# OZ440-SE100-CAR003_sheet7.net
KiCad netlist of a schematic drawn in Altium Designer
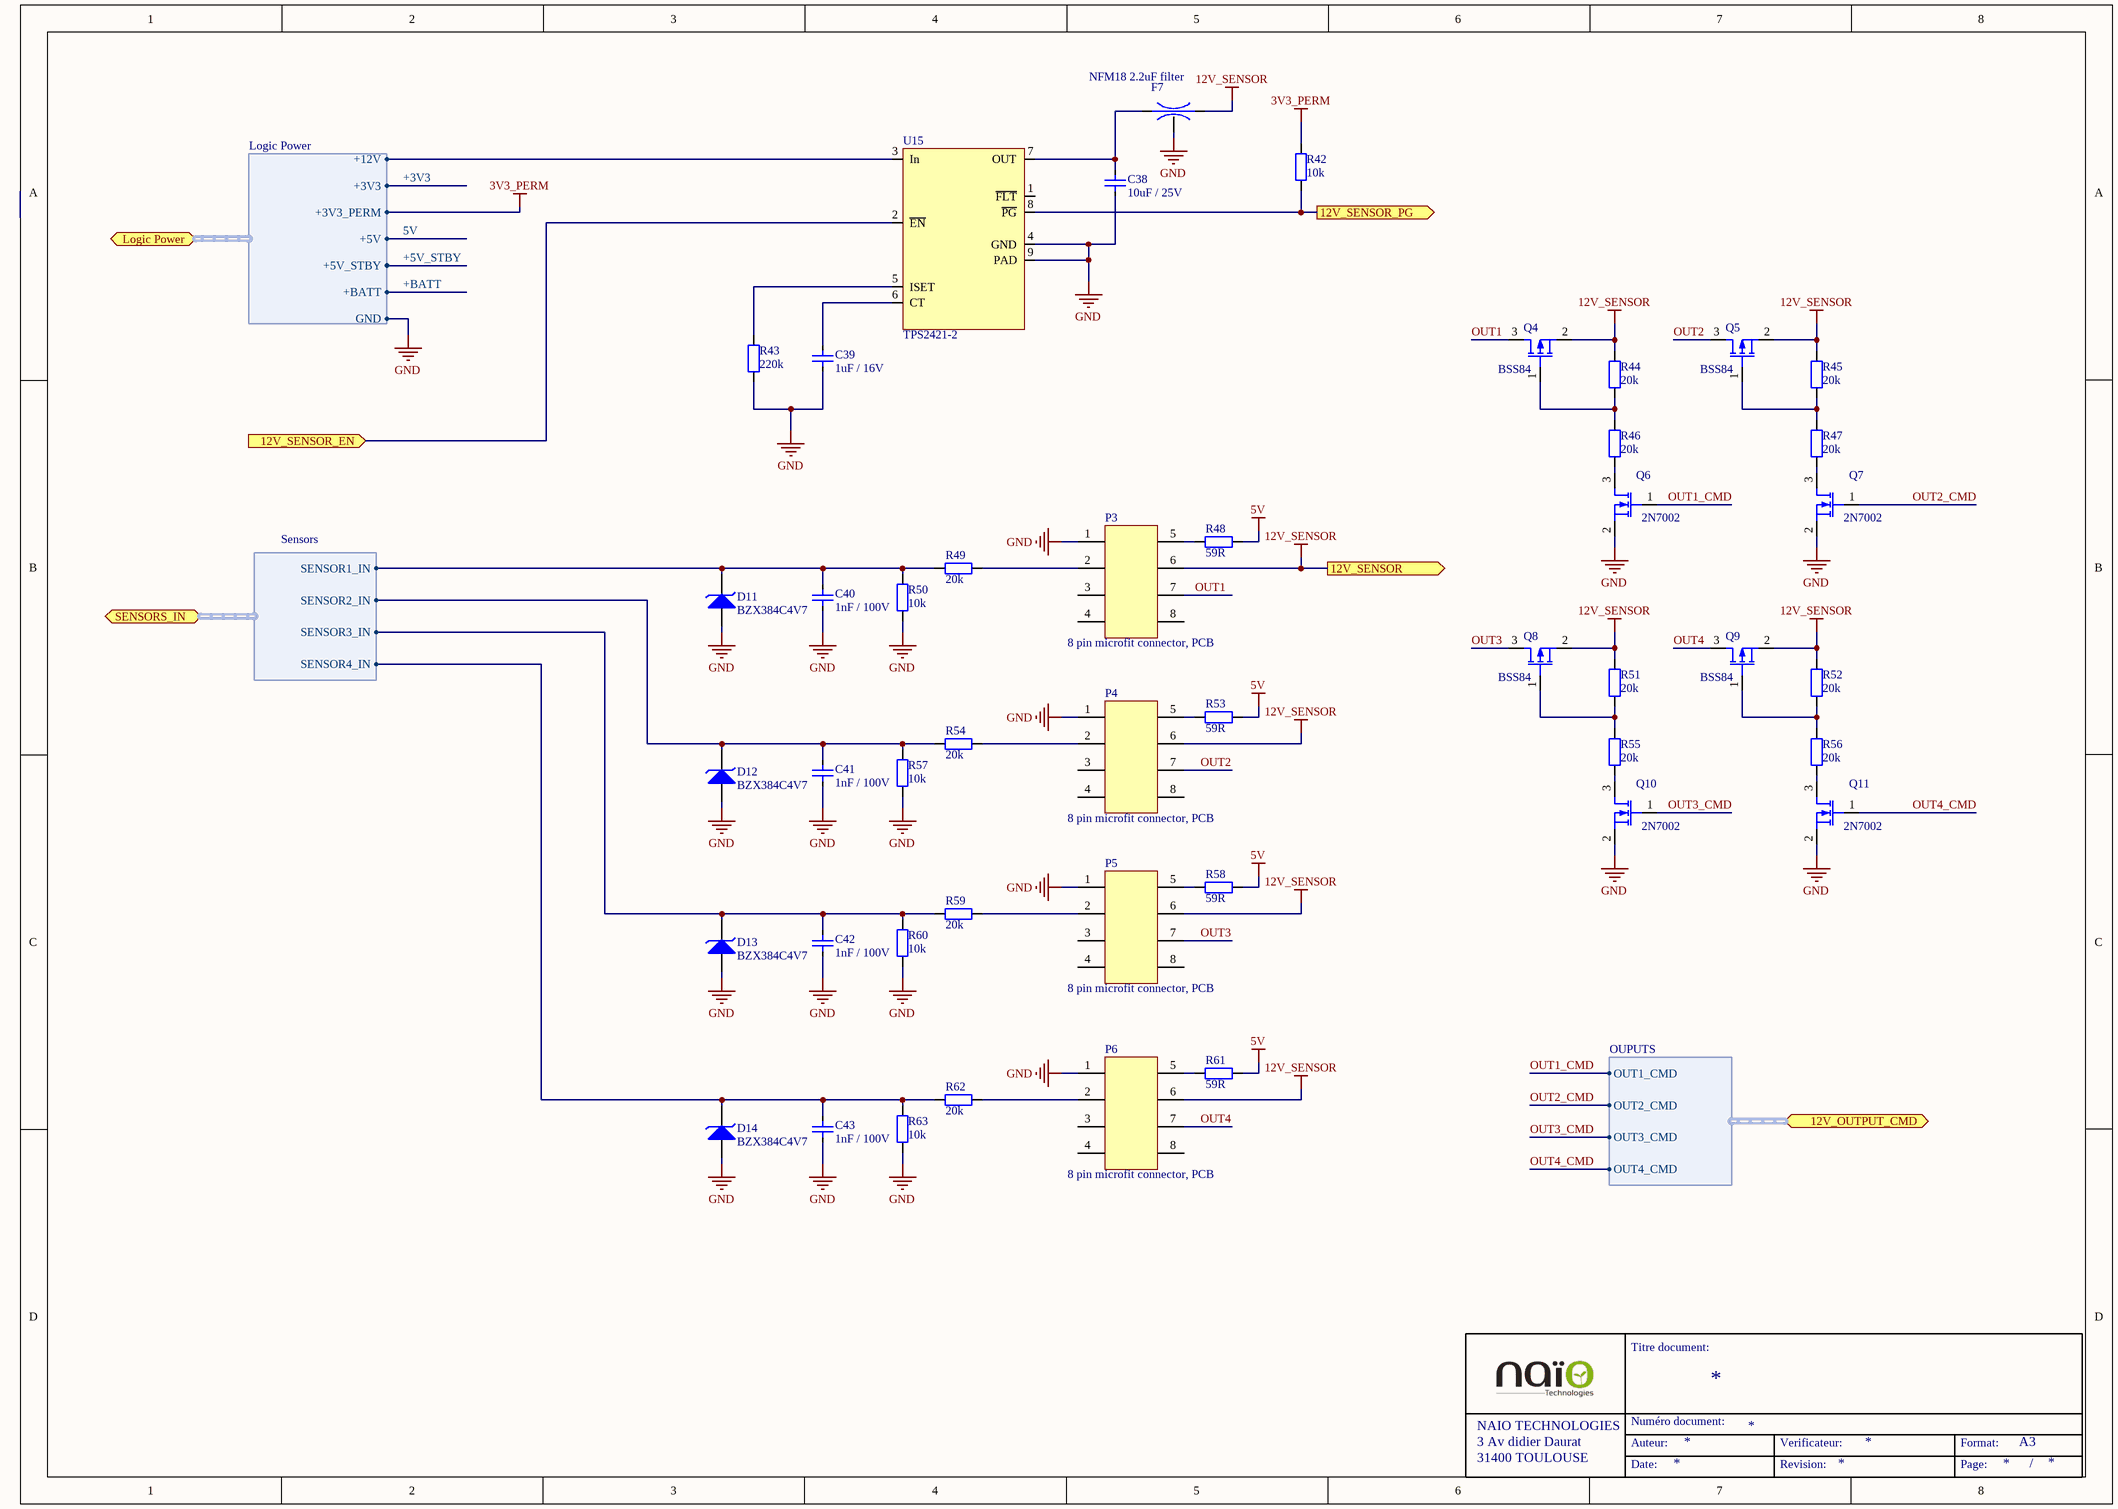
[diagram p0: OZ440-SE100-CAR003_sheet7.SchDoc]

(export (version "E")
  (design (tool "Eeschema 10.0.6"))
  (components
    (comp (ref "C38")
      (value "CAP-SMD")
      (footprint "C1206-STD")
      (description "1206 10uF / 25V X7R ceramic capacitor")
      (fields
        (field (name "DISPLAYED REFERENCE") "10uF / 25V")
        (field (name "TOLERANCE") "+/- 10%")
        (field (name "MANUFACTURER") "Kemet")
      )
      (libsource (lib "lib_NAIO") (part "CAP-SMD"))
    )
    (comp (ref "C39")
      (value "CAP-SMD")
      (footprint "C0805-STD")
      (description "0805 1uF / 16V X7R ceramic capacitor")
      (fields
        (field (name "DISPLAYED REFERENCE") "1uF / 16V")
        (field (name "TOLERANCE") "+/- 10%")
        (field (name "MANUFACTURER") "Kemet")
      )
      (libsource (lib "lib_NAIO") (part "CAP-SMD"))
    )
    (comp (ref "C40")
      (value "CAP-SMD")
      (footprint "C0805-STD")
      (description "0805 1nF / 100V X7R ceramic capacitor")
      (fields
        (field (name "DISPLAYED REFERENCE") "1nF / 100V")
        (field (name "TOLERANCE") "+/- 10%")
        (field (name "MANUFACTURER") "vishay")
      )
      (libsource (lib "lib_NAIO") (part "CAP-SMD"))
    )
    (comp (ref "C41")
      (value "CAP-SMD")
      (footprint "C0805-STD")
      (description "0805 1nF / 100V X7R ceramic capacitor")
      (fields
        (field (name "DISPLAYED REFERENCE") "1nF / 100V")
        (field (name "TOLERANCE") "+/- 10%")
        (field (name "MANUFACTURER") "vishay")
      )
      (libsource (lib "lib_NAIO") (part "CAP-SMD"))
    )
    (comp (ref "C42")
      (value "CAP-SMD")
      (footprint "C0805-STD")
      (description "0805 1nF / 100V X7R ceramic capacitor")
      (fields
        (field (name "DISPLAYED REFERENCE") "1nF / 100V")
        (field (name "TOLERANCE") "+/- 10%")
        (field (name "MANUFACTURER") "vishay")
      )
      (libsource (lib "lib_NAIO") (part "CAP-SMD"))
    )
    (comp (ref "C43")
      (value "CAP-SMD")
      (footprint "C0805-STD")
      (description "0805 1nF / 100V X7R ceramic capacitor")
      (fields
        (field (name "DISPLAYED REFERENCE") "1nF / 100V")
        (field (name "TOLERANCE") "+/- 10%")
        (field (name "MANUFACTURER") "vishay")
      )
      (libsource (lib "lib_NAIO") (part "CAP-SMD"))
    )
    (comp (ref "D11")
      (value "DIODE_ZENER-SOD323")
      (footprint "SOD323-SPE-BZX384")
      (description "4.7V zener diode")
      (fields (field (name "DISPLAYED REFERENCE") "BZX384C4V7") (field (name "MANUFACTURER") "VISHAY"))
      (libsource (lib "lib_NAIO") (part "DIODE_ZENER-SOD323"))
    )
    (comp (ref "D12")
      (value "DIODE_ZENER-SOD323")
      (footprint "SOD323-SPE-BZX384")
      (description "4.7V zener diode")
      (fields (field (name "DISPLAYED REFERENCE") "BZX384C4V7") (field (name "MANUFACTURER") "VISHAY"))
      (libsource (lib "lib_NAIO") (part "DIODE_ZENER-SOD323"))
    )
    (comp (ref "D13")
      (value "DIODE_ZENER-SOD323")
      (footprint "SOD323-SPE-BZX384")
      (description "4.7V zener diode")
      (fields (field (name "DISPLAYED REFERENCE") "BZX384C4V7") (field (name "MANUFACTURER") "VISHAY"))
      (libsource (lib "lib_NAIO") (part "DIODE_ZENER-SOD323"))
    )
    (comp (ref "D14")
      (value "DIODE_ZENER-SOD323")
      (footprint "SOD323-SPE-BZX384")
      (description "4.7V zener diode")
      (fields (field (name "DISPLAYED REFERENCE") "BZX384C4V7") (field (name "MANUFACTURER") "VISHAY"))
      (libsource (lib "lib_NAIO") (part "DIODE_ZENER-SOD323"))
    )
    (comp (ref "F7")
      (value "LC_FILTER-STD")
      (footprint "LC_0603-STD")
      (description "2A LC filter")
      (fields
        (field (name "DISPLAYED REFERENCE") "NFM18 2.2uF filter")
        (field (name "MANUFACTURER") "MURATA")
      )
      (libsource (lib "lib_NAIO") (part "LC_FILTER-STD"))
    )
    (comp (ref "P3")
      (value "CONN-SPE-8P_MOLEX_43045-0801")
      (footprint "CONN-SPE_MOLEX_43045-0801")
      (description "8 pin Microfit connector")
      (fields
        (field (name "DISPLAYED REFERENCE") "8 pin microfit connector, PCB")
        (field (name "MANUFACTURER") "Molex")
      )
      (libsource (lib "lib_NAIO") (part "CONN-SPE-8P_MOLEX_43045-0801"))
    )
    (comp (ref "P4")
      (value "CONN-SPE-8P_MOLEX_43045-0801")
      (footprint "CONN-SPE_MOLEX_43045-0801")
      (description "8 pin Microfit connector")
      (fields
        (field (name "DISPLAYED REFERENCE") "8 pin microfit connector, PCB")
        (field (name "MANUFACTURER") "Molex")
      )
      (libsource (lib "lib_NAIO") (part "CONN-SPE-8P_MOLEX_43045-0801"))
    )
    (comp (ref "P5")
      (value "CONN-SPE-8P_MOLEX_43045-0801")
      (footprint "CONN-SPE_MOLEX_43045-0801")
      (description "8 pin Microfit connector")
      (fields
        (field (name "DISPLAYED REFERENCE") "8 pin microfit connector, PCB")
        (field (name "MANUFACTURER") "Molex")
      )
      (libsource (lib "lib_NAIO") (part "CONN-SPE-8P_MOLEX_43045-0801"))
    )
    (comp (ref "P6")
      (value "CONN-SPE-8P_MOLEX_43045-0801")
      (footprint "CONN-SPE_MOLEX_43045-0801")
      (description "8 pin Microfit connector")
      (fields
        (field (name "DISPLAYED REFERENCE") "8 pin microfit connector, PCB")
        (field (name "MANUFACTURER") "Molex")
      )
      (libsource (lib "lib_NAIO") (part "CONN-SPE-8P_MOLEX_43045-0801"))
    )
    (comp (ref "Q4")
      (value "BSS84-SOT23")
      (footprint "SOT23-STD")
      (description "P-Channel Enhancement Mode Field Effect Transistor")
      (fields (field (name "DISPLAYED REFERENCE") "BSS84") (field (name "MANUFACTURER") "FAIRCHILD"))
      (libsource (lib "lib_NAIO") (part "BSS84-SOT23"))
    )
    (comp (ref "Q5")
      (value "BSS84-SOT23")
      (footprint "SOT23-STD")
      (description "P-Channel Enhancement Mode Field Effect Transistor")
      (fields (field (name "DISPLAYED REFERENCE") "BSS84") (field (name "MANUFACTURER") "FAIRCHILD"))
      (libsource (lib "lib_NAIO") (part "BSS84-SOT23"))
    )
    (comp (ref "Q6")
      (value "2N7002-SMD3P")
      (footprint "SOT23-SPE-2N7002")
      (description "N-Channel Enhancement Mode Field Effect Transistor")
      (fields (field (name "DISPLAYED REFERENCE") "2N7002") (field (name "MANUFACTURER") "FAIRCHILD"))
      (libsource (lib "lib_NAIO") (part "2N7002-SMD3P"))
    )
    (comp (ref "Q7")
      (value "2N7002-SMD3P")
      (footprint "SOT23-SPE-2N7002")
      (description "N-Channel Enhancement Mode Field Effect Transistor")
      (fields (field (name "DISPLAYED REFERENCE") "2N7002") (field (name "MANUFACTURER") "FAIRCHILD"))
      (libsource (lib "lib_NAIO") (part "2N7002-SMD3P"))
    )
    (comp (ref "Q8")
      (value "BSS84-SOT23")
      (footprint "SOT23-STD")
      (description "P-Channel Enhancement Mode Field Effect Transistor")
      (fields (field (name "DISPLAYED REFERENCE") "BSS84") (field (name "MANUFACTURER") "FAIRCHILD"))
      (libsource (lib "lib_NAIO") (part "BSS84-SOT23"))
    )
    (comp (ref "Q9")
      (value "BSS84-SOT23")
      (footprint "SOT23-STD")
      (description "P-Channel Enhancement Mode Field Effect Transistor")
      (fields (field (name "DISPLAYED REFERENCE") "BSS84") (field (name "MANUFACTURER") "FAIRCHILD"))
      (libsource (lib "lib_NAIO") (part "BSS84-SOT23"))
    )
    (comp (ref "Q10")
      (value "2N7002-SMD3P")
      (footprint "SOT23-SPE-2N7002")
      (description "N-Channel Enhancement Mode Field Effect Transistor")
      (fields (field (name "DISPLAYED REFERENCE") "2N7002") (field (name "MANUFACTURER") "FAIRCHILD"))
      (libsource (lib "lib_NAIO") (part "2N7002-SMD3P"))
    )
    (comp (ref "Q11")
      (value "2N7002-SMD3P")
      (footprint "SOT23-SPE-2N7002")
      (description "N-Channel Enhancement Mode Field Effect Transistor")
      (fields (field (name "DISPLAYED REFERENCE") "2N7002") (field (name "MANUFACTURER") "FAIRCHILD"))
      (libsource (lib "lib_NAIO") (part "2N7002-SMD3P"))
    )
    (comp (ref "R42")
      (value "RES-SMD")
      (footprint "R0805-STD")
      (description "10k Ohm 0805 SMD resistor")
      (fields
        (field (name "DISPLAYED REFERENCE") "10k")
        (field (name "TOLERANCE") "1 %")
        (field (name "MANUFACTURER") "Vishay")
      )
      (libsource (lib "") (part "RES-SMD_2"))
    )
    (comp (ref "R43")
      (value "RES-SMD")
      (footprint "R0805-STD")
      (description "220k Ohm 0805 SMD resistor")
      (fields
        (field (name "DISPLAYED REFERENCE") "220k")
        (field (name "TOLERANCE") "1 %")
        (field (name "MANUFACTURER") "Vishay")
      )
      (libsource (lib "lib_NAIO") (part "RES-SMD"))
    )
    (comp (ref "R44")
      (value "RES-SMD")
      (footprint "R0805-STD")
      (description "20k Ohm 0805 SMD resistor")
      (fields
        (field (name "DISPLAYED REFERENCE") "20k")
        (field (name "TOLERANCE") "1 %")
        (field (name "MANUFACTURER") "Vishay")
      )
      (libsource (lib "lib_NAIO") (part "RES-SMD"))
    )
    (comp (ref "R45")
      (value "RES-SMD")
      (footprint "R0805-STD")
      (description "20k Ohm 0805 SMD resistor")
      (fields
        (field (name "DISPLAYED REFERENCE") "20k")
        (field (name "TOLERANCE") "1 %")
        (field (name "MANUFACTURER") "Vishay")
      )
      (libsource (lib "lib_NAIO") (part "RES-SMD"))
    )
    (comp (ref "R46")
      (value "RES-SMD")
      (footprint "R0805-STD")
      (description "20k Ohm 0805 SMD resistor")
      (fields
        (field (name "DISPLAYED REFERENCE") "20k")
        (field (name "TOLERANCE") "1 %")
        (field (name "MANUFACTURER") "Vishay")
      )
      (libsource (lib "lib_NAIO") (part "RES-SMD"))
    )
    (comp (ref "R47")
      (value "RES-SMD")
      (footprint "R0805-STD")
      (description "20k Ohm 0805 SMD resistor")
      (fields
        (field (name "DISPLAYED REFERENCE") "20k")
        (field (name "TOLERANCE") "1 %")
        (field (name "MANUFACTURER") "Vishay")
      )
      (libsource (lib "lib_NAIO") (part "RES-SMD"))
    )
    (comp (ref "R48")
      (value "RES-SMD")
      (footprint "R0805-STD")
      (description "59 Ohm 0805 SMD resistor")
      (fields
        (field (name "DISPLAYED REFERENCE") "59R")
        (field (name "TOLERANCE") "1 %")
        (field (name "MANUFACTURER") "Vishay")
      )
      (libsource (lib "") (part "RES-SMD_1"))
    )
    (comp (ref "R49")
      (value "RES-SMD")
      (footprint "R0805-STD")
      (description "20k Ohm 0805 SMD resistor")
      (fields
        (field (name "DISPLAYED REFERENCE") "20k")
        (field (name "TOLERANCE") "1 %")
        (field (name "MANUFACTURER") "Vishay")
      )
      (libsource (lib "") (part "RES-SMD_1"))
    )
    (comp (ref "R50")
      (value "RES-SMD")
      (footprint "R0805-STD")
      (description "10k Ohm 0805 SMD resistor")
      (fields
        (field (name "DISPLAYED REFERENCE") "10k")
        (field (name "TOLERANCE") "1 %")
        (field (name "MANUFACTURER") "Vishay")
      )
      (libsource (lib "lib_NAIO") (part "RES-SMD"))
    )
    (comp (ref "R51")
      (value "RES-SMD")
      (footprint "R0805-STD")
      (description "20k Ohm 0805 SMD resistor")
      (fields
        (field (name "DISPLAYED REFERENCE") "20k")
        (field (name "TOLERANCE") "1 %")
        (field (name "MANUFACTURER") "Vishay")
      )
      (libsource (lib "lib_NAIO") (part "RES-SMD"))
    )
    (comp (ref "R52")
      (value "RES-SMD")
      (footprint "R0805-STD")
      (description "20k Ohm 0805 SMD resistor")
      (fields
        (field (name "DISPLAYED REFERENCE") "20k")
        (field (name "TOLERANCE") "1 %")
        (field (name "MANUFACTURER") "Vishay")
      )
      (libsource (lib "lib_NAIO") (part "RES-SMD"))
    )
    (comp (ref "R53")
      (value "RES-SMD")
      (footprint "R0805-STD")
      (description "59 Ohm 0805 SMD resistor")
      (fields
        (field (name "DISPLAYED REFERENCE") "59R")
        (field (name "TOLERANCE") "1 %")
        (field (name "MANUFACTURER") "Vishay")
      )
      (libsource (lib "") (part "RES-SMD_1"))
    )
    (comp (ref "R54")
      (value "RES-SMD")
      (footprint "R0805-STD")
      (description "20k Ohm 0805 SMD resistor")
      (fields
        (field (name "DISPLAYED REFERENCE") "20k")
        (field (name "TOLERANCE") "1 %")
        (field (name "MANUFACTURER") "Vishay")
      )
      (libsource (lib "") (part "RES-SMD_1"))
    )
    (comp (ref "R55")
      (value "RES-SMD")
      (footprint "R0805-STD")
      (description "20k Ohm 0805 SMD resistor")
      (fields
        (field (name "DISPLAYED REFERENCE") "20k")
        (field (name "TOLERANCE") "1 %")
        (field (name "MANUFACTURER") "Vishay")
      )
      (libsource (lib "lib_NAIO") (part "RES-SMD"))
    )
    (comp (ref "R56")
      (value "RES-SMD")
      (footprint "R0805-STD")
      (description "20k Ohm 0805 SMD resistor")
      (fields
        (field (name "DISPLAYED REFERENCE") "20k")
        (field (name "TOLERANCE") "1 %")
        (field (name "MANUFACTURER") "Vishay")
      )
      (libsource (lib "lib_NAIO") (part "RES-SMD"))
    )
    (comp (ref "R57")
      (value "RES-SMD")
      (footprint "R0805-STD")
      (description "10k Ohm 0805 SMD resistor")
      (fields
        (field (name "DISPLAYED REFERENCE") "10k")
        (field (name "TOLERANCE") "1 %")
        (field (name "MANUFACTURER") "Vishay")
      )
      (libsource (lib "lib_NAIO") (part "RES-SMD"))
    )
    (comp (ref "R58")
      (value "RES-SMD")
      (footprint "R0805-STD")
      (description "59 Ohm 0805 SMD resistor")
      (fields
        (field (name "DISPLAYED REFERENCE") "59R")
        (field (name "TOLERANCE") "1 %")
        (field (name "MANUFACTURER") "Vishay")
      )
      (libsource (lib "") (part "RES-SMD_1"))
    )
    (comp (ref "R59")
      (value "RES-SMD")
      (footprint "R0805-STD")
      (description "20k Ohm 0805 SMD resistor")
      (fields
        (field (name "DISPLAYED REFERENCE") "20k")
        (field (name "TOLERANCE") "1 %")
        (field (name "MANUFACTURER") "Vishay")
      )
      (libsource (lib "") (part "RES-SMD_1"))
    )
    (comp (ref "R60")
      (value "RES-SMD")
      (footprint "R0805-STD")
      (description "10k Ohm 0805 SMD resistor")
      (fields
        (field (name "DISPLAYED REFERENCE") "10k")
        (field (name "TOLERANCE") "1 %")
        (field (name "MANUFACTURER") "Vishay")
      )
      (libsource (lib "lib_NAIO") (part "RES-SMD"))
    )
    (comp (ref "R61")
      (value "RES-SMD")
      (footprint "R0805-STD")
      (description "59 Ohm 0805 SMD resistor")
      (fields
        (field (name "DISPLAYED REFERENCE") "59R")
        (field (name "TOLERANCE") "1 %")
        (field (name "MANUFACTURER") "Vishay")
      )
      (libsource (lib "") (part "RES-SMD_1"))
    )
    (comp (ref "R62")
      (value "RES-SMD")
      (footprint "R0805-STD")
      (description "20k Ohm 0805 SMD resistor")
      (fields
        (field (name "DISPLAYED REFERENCE") "20k")
        (field (name "TOLERANCE") "1 %")
        (field (name "MANUFACTURER") "Vishay")
      )
      (libsource (lib "") (part "RES-SMD_1"))
    )
    (comp (ref "R63")
      (value "RES-SMD")
      (footprint "R0805-STD")
      (description "10k Ohm 0805 SMD resistor")
      (fields
        (field (name "DISPLAYED REFERENCE") "10k")
        (field (name "TOLERANCE") "1 %")
        (field (name "MANUFACTURER") "Vishay")
      )
      (libsource (lib "lib_NAIO") (part "RES-SMD"))
    )
    (comp (ref "U15")
      (value "TPS2421-SO8")
      (footprint "SO8_THERMAL-STD")
      (description "20V-5A Hot plug controller with integrated FET, auto retry")
      (fields (field (name "DISPLAYED REFERENCE") "TPS2421-2") (field (name "MANUFACTURER") "TI"))
      (libsource (lib "lib_NAIO") (part "TPS2421-SO8"))
    )
  )
  (nets
    (net (code "7") (name "/+12V") (class "Default")
      (node (ref "U15") (pin "3") (pinfunction "In_3") (pintype "passive"))
    )
    (net (code "9") (name "/12V_SENSOR_EN") (class "Default")
      (node (ref "U15") (pin "2") (pinfunction "EN_2") (pintype "passive"))
    )
    (net (code "10") (name "/12V_SENSOR_PG") (class "Default")
      (node (ref "R42") (pin "2") (pinfunction "2_2") (pintype "passive"))
      (node (ref "U15") (pin "8") (pinfunction "PG_8") (pintype "passive"))
    )
    (net (code "11") (name "/OUT1") (class "Default")
      (node (ref "P3") (pin "7") (pinfunction "7_7") (pintype "passive"))
      (node (ref "Q4") (pin "3") (pinfunction "D_3") (pintype "passive"))
    )
    (net (code "12") (name "/OUT1_CMD") (class "Default")
      (node (ref "Q6") (pin "1") (pinfunction "G_1") (pintype "passive"))
    )
    (net (code "13") (name "/OUT2") (class "Default")
      (node (ref "P4") (pin "7") (pinfunction "7_7") (pintype "passive"))
      (node (ref "Q5") (pin "3") (pinfunction "D_3") (pintype "passive"))
    )
    (net (code "14") (name "/OUT2_CMD") (class "Default")
      (node (ref "Q7") (pin "1") (pinfunction "G_1") (pintype "passive"))
    )
    (net (code "15") (name "/OUT3") (class "Default")
      (node (ref "P5") (pin "7") (pinfunction "7_7") (pintype "passive"))
      (node (ref "Q8") (pin "3") (pinfunction "D_3") (pintype "passive"))
    )
    (net (code "16") (name "/OUT3_CMD") (class "Default")
      (node (ref "Q10") (pin "1") (pinfunction "G_1") (pintype "passive"))
    )
    (net (code "17") (name "/OUT4") (class "Default")
      (node (ref "P6") (pin "7") (pinfunction "7_7") (pintype "passive"))
      (node (ref "Q9") (pin "3") (pinfunction "D_3") (pintype "passive"))
    )
    (net (code "18") (name "/OUT4_CMD") (class "Default")
      (node (ref "Q11") (pin "1") (pinfunction "G_1") (pintype "passive"))
    )
    (net (code "19") (name "/SENSOR1_IN") (class "Default")
      (node (ref "C40") (pin "2") (pinfunction "2_2") (pintype "passive"))
      (node (ref "D11") (pin "K") (pinfunction "K_K") (pintype "passive"))
      (node (ref "R49") (pin "1") (pinfunction "1_1") (pintype "passive"))
      (node (ref "R50") (pin "2") (pinfunction "2_2") (pintype "passive"))
    )
    (net (code "20") (name "/SENSOR2_IN") (class "Default")
      (node (ref "C41") (pin "2") (pinfunction "2_2") (pintype "passive"))
      (node (ref "D12") (pin "K") (pinfunction "K_K") (pintype "passive"))
      (node (ref "R54") (pin "1") (pinfunction "1_1") (pintype "passive"))
      (node (ref "R57") (pin "2") (pinfunction "2_2") (pintype "passive"))
    )
    (net (code "21") (name "/SENSOR3_IN") (class "Default")
      (node (ref "C42") (pin "2") (pinfunction "2_2") (pintype "passive"))
      (node (ref "D13") (pin "K") (pinfunction "K_K") (pintype "passive"))
      (node (ref "R59") (pin "1") (pinfunction "1_1") (pintype "passive"))
      (node (ref "R60") (pin "2") (pinfunction "2_2") (pintype "passive"))
    )
    (net (code "22") (name "/SENSOR4_IN") (class "Default")
      (node (ref "C43") (pin "2") (pinfunction "2_2") (pintype "passive"))
      (node (ref "D14") (pin "K") (pinfunction "K_K") (pintype "passive"))
      (node (ref "R62") (pin "1") (pinfunction "1_1") (pintype "passive"))
      (node (ref "R63") (pin "2") (pinfunction "2_2") (pintype "passive"))
    )
    (net (code "26") (name "3V3_PERM") (class "Default")
      (node (ref "R42") (pin "1") (pinfunction "1_1") (pintype "passive"))
    )
    (net (code "27") (name "5V") (class "Default")
      (node (ref "R48") (pin "2") (pinfunction "2_2") (pintype "passive"))
      (node (ref "R53") (pin "2") (pinfunction "2_2") (pintype "passive"))
      (node (ref "R58") (pin "2") (pinfunction "2_2") (pintype "passive"))
      (node (ref "R61") (pin "2") (pinfunction "2_2") (pintype "passive"))
    )
    (net (code "28") (name "12V_SENSOR") (class "Default")
      (node (ref "F7") (pin "2") (pinfunction "B_2") (pintype "passive"))
      (node (ref "P3") (pin "6") (pinfunction "6_6") (pintype "passive"))
      (node (ref "P4") (pin "6") (pinfunction "6_6") (pintype "passive"))
      (node (ref "P5") (pin "6") (pinfunction "6_6") (pintype "passive"))
      (node (ref "P6") (pin "6") (pinfunction "6_6") (pintype "passive"))
      (node (ref "Q4") (pin "2") (pinfunction "S_2") (pintype "passive"))
      (node (ref "Q5") (pin "2") (pinfunction "S_2") (pintype "passive"))
      (node (ref "Q8") (pin "2") (pinfunction "S_2") (pintype "passive"))
      (node (ref "Q9") (pin "2") (pinfunction "S_2") (pintype "passive"))
      (node (ref "R44") (pin "2") (pinfunction "2_2") (pintype "passive"))
      (node (ref "R45") (pin "2") (pinfunction "2_2") (pintype "passive"))
      (node (ref "R51") (pin "2") (pinfunction "2_2") (pintype "passive"))
      (node (ref "R52") (pin "2") (pinfunction "2_2") (pintype "passive"))
    )
    (net (code "29") (name "GND") (class "Default")
      (node (ref "C38") (pin "1") (pinfunction "1_1") (pintype "passive"))
      (node (ref "C39") (pin "1") (pinfunction "1_1") (pintype "passive"))
      (node (ref "C40") (pin "1") (pinfunction "1_1") (pintype "passive"))
      (node (ref "C41") (pin "1") (pinfunction "1_1") (pintype "passive"))
      (node (ref "C42") (pin "1") (pinfunction "1_1") (pintype "passive"))
      (node (ref "C43") (pin "1") (pinfunction "1_1") (pintype "passive"))
      (node (ref "D11") (pin "A") (pinfunction "A_A") (pintype "passive"))
      (node (ref "D12") (pin "A") (pinfunction "A_A") (pintype "passive"))
      (node (ref "D13") (pin "A") (pinfunction "A_A") (pintype "passive"))
      (node (ref "D14") (pin "A") (pinfunction "A_A") (pintype "passive"))
      (node (ref "F7") (pin "3") (pinfunction "G_3") (pintype "passive"))
      (node (ref "P3") (pin "1") (pinfunction "1_1") (pintype "passive"))
      (node (ref "P4") (pin "1") (pinfunction "1_1") (pintype "passive"))
      (node (ref "P5") (pin "1") (pinfunction "1_1") (pintype "passive"))
      (node (ref "P6") (pin "1") (pinfunction "1_1") (pintype "passive"))
      (node (ref "Q10") (pin "2") (pinfunction "S_2") (pintype "passive"))
      (node (ref "Q11") (pin "2") (pinfunction "S_2") (pintype "passive"))
      (node (ref "Q6") (pin "2") (pinfunction "S_2") (pintype "passive"))
      (node (ref "Q7") (pin "2") (pinfunction "S_2") (pintype "passive"))
      (node (ref "R43") (pin "1") (pinfunction "1_1") (pintype "passive"))
      (node (ref "R50") (pin "1") (pinfunction "1_1") (pintype "passive"))
      (node (ref "R57") (pin "1") (pinfunction "1_1") (pintype "passive"))
      (node (ref "R60") (pin "1") (pinfunction "1_1") (pintype "passive"))
      (node (ref "R63") (pin "1") (pinfunction "1_1") (pintype "passive"))
      (node (ref "U15") (pin "4") (pinfunction "GND_4") (pintype "passive"))
      (node (ref "U15") (pin "9") (pinfunction "PAD_9") (pintype "passive"))
    )
    (net (code "30") (name "Net-(F7-A)") (class "Default")
      (node (ref "C38") (pin "2") (pinfunction "2_2") (pintype "passive"))
      (node (ref "F7") (pin "1") (pinfunction "A_1") (pintype "passive"))
      (node (ref "U15") (pin "7") (pinfunction "OUT_7") (pintype "passive"))
    )
    (net (code "31") (name "Net-(P3-9)") (class "Default")
      (node (ref "P3") (pin "5") (pinfunction "9_5") (pintype "passive"))
      (node (ref "R48") (pin "1") (pinfunction "1_1") (pintype "passive"))
    )
    (net (code "32") (name "Net-(P3-Pad2)") (class "Default")
      (node (ref "P3") (pin "2") (pinfunction "2_2") (pintype "passive"))
      (node (ref "R49") (pin "2") (pinfunction "2_2") (pintype "passive"))
    )
    (net (code "33") (name "Net-(P4-9)") (class "Default")
      (node (ref "P4") (pin "5") (pinfunction "9_5") (pintype "passive"))
      (node (ref "R53") (pin "1") (pinfunction "1_1") (pintype "passive"))
    )
    (net (code "34") (name "Net-(P4-Pad2)") (class "Default")
      (node (ref "P4") (pin "2") (pinfunction "2_2") (pintype "passive"))
      (node (ref "R54") (pin "2") (pinfunction "2_2") (pintype "passive"))
    )
    (net (code "35") (name "Net-(P5-9)") (class "Default")
      (node (ref "P5") (pin "5") (pinfunction "9_5") (pintype "passive"))
      (node (ref "R58") (pin "1") (pinfunction "1_1") (pintype "passive"))
    )
    (net (code "36") (name "Net-(P5-Pad2)") (class "Default")
      (node (ref "P5") (pin "2") (pinfunction "2_2") (pintype "passive"))
      (node (ref "R59") (pin "2") (pinfunction "2_2") (pintype "passive"))
    )
    (net (code "37") (name "Net-(P6-9)") (class "Default")
      (node (ref "P6") (pin "5") (pinfunction "9_5") (pintype "passive"))
      (node (ref "R61") (pin "1") (pinfunction "1_1") (pintype "passive"))
    )
    (net (code "38") (name "Net-(P6-Pad2)") (class "Default")
      (node (ref "P6") (pin "2") (pinfunction "2_2") (pintype "passive"))
      (node (ref "R62") (pin "2") (pinfunction "2_2") (pintype "passive"))
    )
    (net (code "39") (name "Net-(Q4-G)") (class "Default")
      (node (ref "Q4") (pin "1") (pinfunction "G_1") (pintype "passive"))
      (node (ref "R44") (pin "1") (pinfunction "1_1") (pintype "passive"))
      (node (ref "R46") (pin "2") (pinfunction "2_2") (pintype "passive"))
    )
    (net (code "40") (name "Net-(Q5-G)") (class "Default")
      (node (ref "Q5") (pin "1") (pinfunction "G_1") (pintype "passive"))
      (node (ref "R45") (pin "1") (pinfunction "1_1") (pintype "passive"))
      (node (ref "R47") (pin "2") (pinfunction "2_2") (pintype "passive"))
    )
    (net (code "41") (name "Net-(Q6-D)") (class "Default")
      (node (ref "Q6") (pin "3") (pinfunction "D_3") (pintype "passive"))
      (node (ref "R46") (pin "1") (pinfunction "1_1") (pintype "passive"))
    )
    (net (code "42") (name "Net-(Q7-D)") (class "Default")
      (node (ref "Q7") (pin "3") (pinfunction "D_3") (pintype "passive"))
      (node (ref "R47") (pin "1") (pinfunction "1_1") (pintype "passive"))
    )
    (net (code "43") (name "Net-(Q8-G)") (class "Default")
      (node (ref "Q8") (pin "1") (pinfunction "G_1") (pintype "passive"))
      (node (ref "R51") (pin "1") (pinfunction "1_1") (pintype "passive"))
      (node (ref "R55") (pin "2") (pinfunction "2_2") (pintype "passive"))
    )
    (net (code "44") (name "Net-(Q9-G)") (class "Default")
      (node (ref "Q9") (pin "1") (pinfunction "G_1") (pintype "passive"))
      (node (ref "R52") (pin "1") (pinfunction "1_1") (pintype "passive"))
      (node (ref "R56") (pin "2") (pinfunction "2_2") (pintype "passive"))
    )
    (net (code "45") (name "Net-(Q10-D)") (class "Default")
      (node (ref "Q10") (pin "3") (pinfunction "D_3") (pintype "passive"))
      (node (ref "R55") (pin "1") (pinfunction "1_1") (pintype "passive"))
    )
    (net (code "46") (name "Net-(Q11-D)") (class "Default")
      (node (ref "Q11") (pin "3") (pinfunction "D_3") (pintype "passive"))
      (node (ref "R56") (pin "1") (pinfunction "1_1") (pintype "passive"))
    )
    (net (code "47") (name "Net-(U15-CT)") (class "Default")
      (node (ref "C39") (pin "2") (pinfunction "2_2") (pintype "passive"))
      (node (ref "U15") (pin "6") (pinfunction "CT_6") (pintype "passive"))
    )
    (net (code "48") (name "Net-(U15-ISET)") (class "Default")
      (node (ref "R43") (pin "2") (pinfunction "2_2") (pintype "passive"))
      (node (ref "U15") (pin "5") (pinfunction "ISET_5") (pintype "passive"))
    )
    (net (code "49") (name "unconnected-(P3-7-Pad4)") (class "Default")
      (node (ref "P3") (pin "4") (pinfunction "7_4") (pintype "passive"))
    )
    (net (code "50") (name "unconnected-(P3-Pad3)") (class "Default")
      (node (ref "P3") (pin "3") (pinfunction "3_3") (pintype "passive"))
    )
    (net (code "51") (name "unconnected-(P3-Pad8)") (class "Default")
      (node (ref "P3") (pin "8") (pinfunction "8_8") (pintype "passive"))
    )
    (net (code "52") (name "unconnected-(P4-7-Pad4)") (class "Default")
      (node (ref "P4") (pin "4") (pinfunction "7_4") (pintype "passive"))
    )
    (net (code "53") (name "unconnected-(P4-Pad3)") (class "Default")
      (node (ref "P4") (pin "3") (pinfunction "3_3") (pintype "passive"))
    )
    (net (code "54") (name "unconnected-(P4-Pad8)") (class "Default")
      (node (ref "P4") (pin "8") (pinfunction "8_8") (pintype "passive"))
    )
    (net (code "55") (name "unconnected-(P5-7-Pad4)") (class "Default")
      (node (ref "P5") (pin "4") (pinfunction "7_4") (pintype "passive"))
    )
    (net (code "56") (name "unconnected-(P5-Pad3)") (class "Default")
      (node (ref "P5") (pin "3") (pinfunction "3_3") (pintype "passive"))
    )
    (net (code "57") (name "unconnected-(P5-Pad8)") (class "Default")
      (node (ref "P5") (pin "8") (pinfunction "8_8") (pintype "passive"))
    )
    (net (code "58") (name "unconnected-(P6-7-Pad4)") (class "Default")
      (node (ref "P6") (pin "4") (pinfunction "7_4") (pintype "passive"))
    )
    (net (code "59") (name "unconnected-(P6-Pad3)") (class "Default")
      (node (ref "P6") (pin "3") (pinfunction "3_3") (pintype "passive"))
    )
    (net (code "60") (name "unconnected-(P6-Pad8)") (class "Default")
      (node (ref "P6") (pin "8") (pinfunction "8_8") (pintype "passive"))
    )
    (net (code "61") (name "unconnected-(U15-FLT-Pad1)") (class "Default")
      (node (ref "U15") (pin "1") (pinfunction "FLT_1") (pintype "passive"))
    )
  )
)
